# YOTSUBA_AP_EM_ver_1_1.net
KiCad netlist of a schematic drawn in EAGLE
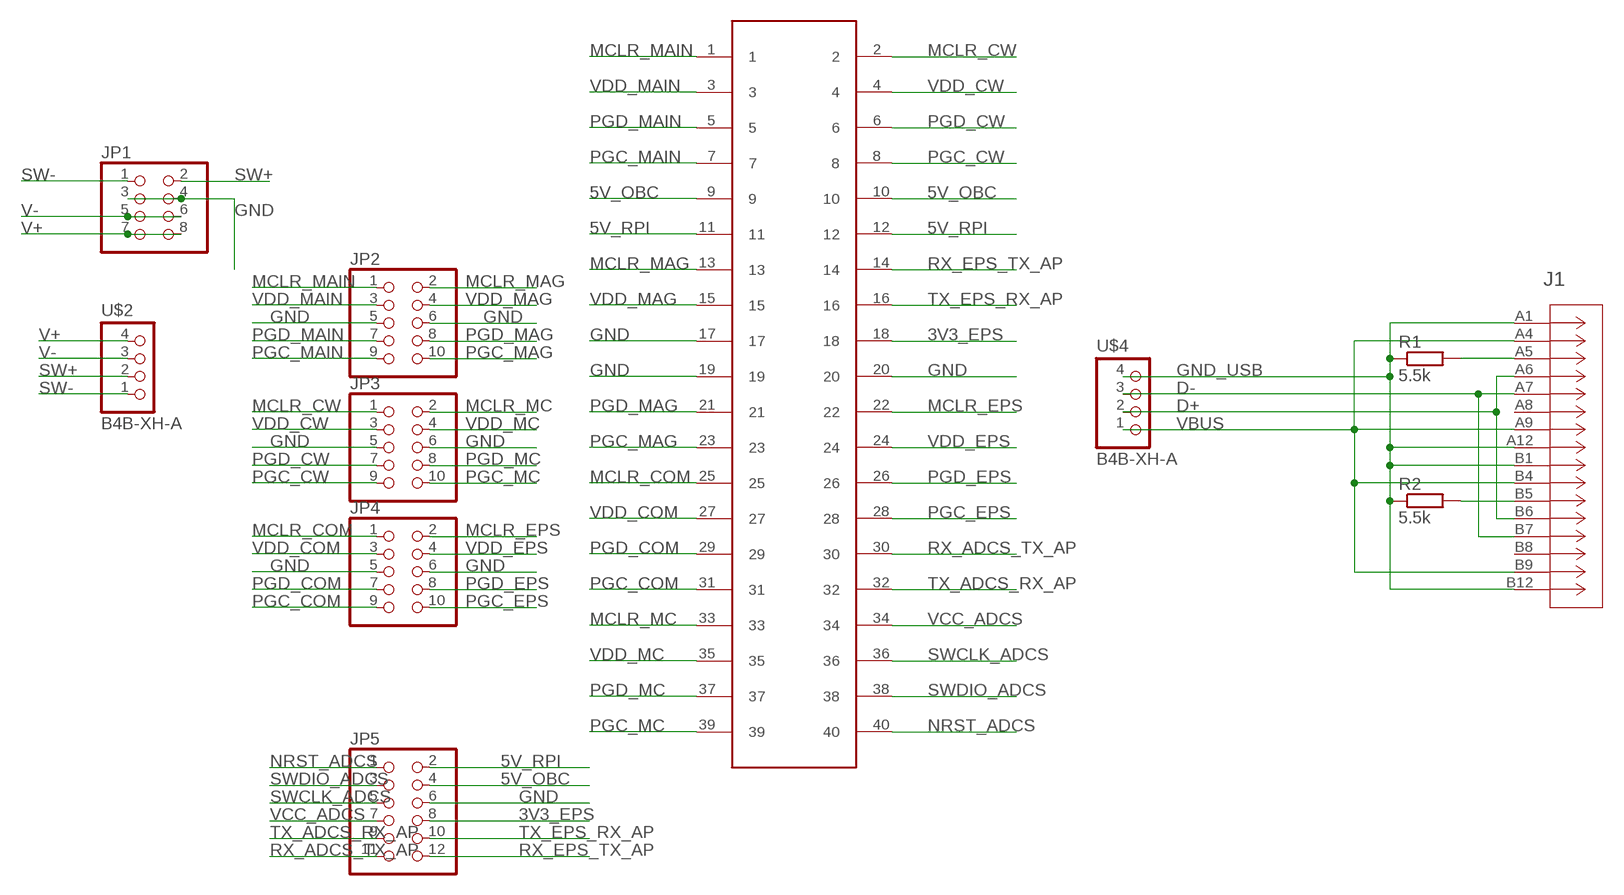
[diagram p0: schematic, sheet 1]

(export (version "E")
  (design (tool "Eeschema 10.0.6"))
  (components
    (comp (ref "J1")
      (value "217182-0001")
      (footprint "eagle-import:CONN_217182-0001_MOL")
      (fields (field (name "COPYRIGHT") "Copyright (C) 2022 Ultra Librarian. All rights reserved."))
      (libsource (lib "eagle-import") (part "217182-0001"))
    )
    (comp (ref "JP1")
      (value "PINHD-2X4")
      (footprint "eagle-import:2X04")
      (libsource (lib "eagle-import") (part "PINHD-2X4"))
    )
    (comp (ref "JP2")
      (value "PINHD-2X5")
      (footprint "eagle-import:2X05")
      (libsource (lib "eagle-import") (part "PINHD-2X5"))
    )
    (comp (ref "JP3")
      (value "PINHD-2X5")
      (footprint "eagle-import:2X05")
      (libsource (lib "eagle-import") (part "PINHD-2X5"))
    )
    (comp (ref "JP4")
      (value "PINHD-2X5")
      (footprint "eagle-import:2X05")
      (libsource (lib "eagle-import") (part "PINHD-2X5"))
    )
    (comp (ref "JP5")
      (value "PINHD-2X6")
      (footprint "eagle-import:2X06")
      (libsource (lib "eagle-import") (part "PINHD-2X6"))
    )
    (comp (ref "R1")
      (value "5.5k")
      (footprint "eagle-import:M2012")
      (libsource (lib "eagle-import") (part "R-EU_M2012"))
    )
    (comp (ref "R2")
      (value "5.5k")
      (footprint "eagle-import:M2012")
      (libsource (lib "eagle-import") (part "R-EU_M2012"))
    )
    (comp (ref "U$1")
      (value "M50-3902042")
      (footprint "eagle-import:M50-3902042")
      (libsource (lib "eagle-import") (part "M50-3902042"))
    )
    (comp (ref "U$2")
      (value "B4B-XH-A")
      (footprint "eagle-import:B4B-XH-A")
      (libsource (lib "eagle-import") (part "B4B-XH-A"))
    )
    (comp (ref "U$4")
      (value "B4B-XH-A")
      (footprint "eagle-import:B4B-XH-A")
      (libsource (lib "eagle-import") (part "B4B-XH-A"))
    )
  )
  (nets
    (net (code "1") (name "/3V3_EPS") (class "Default")
      (node (ref "JP5") (pin "8") (pinfunction "8_8") (pintype "passive"))
      (node (ref "U$1") (pin "18") (pinfunction "18_18") (pintype "bidirectional"))
    )
    (net (code "2") (name "/5V_OBC") (class "Default")
      (node (ref "JP5") (pin "4") (pinfunction "4_4") (pintype "passive"))
      (node (ref "U$1") (pin "10") (pinfunction "10_10") (pintype "bidirectional"))
      (node (ref "U$1") (pin "9") (pinfunction "9_9") (pintype "bidirectional"))
    )
    (net (code "3") (name "/5V_RPI") (class "Default")
      (node (ref "JP5") (pin "2") (pinfunction "2_2") (pintype "passive"))
      (node (ref "U$1") (pin "11") (pinfunction "11_11") (pintype "bidirectional"))
      (node (ref "U$1") (pin "12") (pinfunction "12_12") (pintype "bidirectional"))
    )
    (net (code "4") (name "/D+") (class "Default")
      (node (ref "J1") (pin "A6") (pinfunction "DP1_A6") (pintype "bidirectional"))
      (node (ref "J1") (pin "B6") (pinfunction "DP2_B6") (pintype "bidirectional"))
      (node (ref "U$4") (pin "2") (pinfunction "2_2") (pintype "passive"))
    )
    (net (code "5") (name "/D-") (class "Default")
      (node (ref "J1") (pin "A7") (pinfunction "DN1_A7") (pintype "bidirectional"))
      (node (ref "J1") (pin "B7") (pinfunction "DN2_B7") (pintype "bidirectional"))
      (node (ref "U$4") (pin "3") (pinfunction "3_3") (pintype "passive"))
    )
    (net (code "6") (name "/GND") (class "Default")
      (node (ref "JP1") (pin "3") (pinfunction "3_3") (pintype "passive"))
      (node (ref "JP1") (pin "4") (pinfunction "4_4") (pintype "passive"))
      (node (ref "JP2") (pin "5") (pinfunction "5_5") (pintype "passive"))
      (node (ref "JP2") (pin "6") (pinfunction "6_6") (pintype "passive"))
      (node (ref "JP3") (pin "5") (pinfunction "5_5") (pintype "passive"))
      (node (ref "JP3") (pin "6") (pinfunction "6_6") (pintype "passive"))
      (node (ref "JP4") (pin "5") (pinfunction "5_5") (pintype "passive"))
      (node (ref "JP4") (pin "6") (pinfunction "6_6") (pintype "passive"))
      (node (ref "JP5") (pin "6") (pinfunction "6_6") (pintype "passive"))
      (node (ref "U$1") (pin "17") (pinfunction "17_17") (pintype "bidirectional"))
      (node (ref "U$1") (pin "19") (pinfunction "19_19") (pintype "bidirectional"))
      (node (ref "U$1") (pin "20") (pinfunction "20_20") (pintype "bidirectional"))
    )
    (net (code "7") (name "/GND_USB") (class "Default")
      (node (ref "J1") (pin "A1") (pinfunction "GND_2_A1") (pintype "passive"))
      (node (ref "J1") (pin "A12") (pinfunction "GND_3_A12") (pintype "passive"))
      (node (ref "J1") (pin "B1") (pinfunction "GND_4_B1") (pintype "passive"))
      (node (ref "J1") (pin "B12") (pinfunction "GND_B12") (pintype "passive"))
      (node (ref "R1") (pin "1") (pinfunction "1_1") (pintype "passive"))
      (node (ref "R2") (pin "1") (pinfunction "1_1") (pintype "passive"))
      (node (ref "U$4") (pin "4") (pinfunction "4_4") (pintype "passive"))
    )
    (net (code "8") (name "/MCLR_COM") (class "Default")
      (node (ref "JP4") (pin "1") (pinfunction "1_1") (pintype "passive"))
      (node (ref "U$1") (pin "25") (pinfunction "25_25") (pintype "bidirectional"))
    )
    (net (code "9") (name "/MCLR_CW") (class "Default")
      (node (ref "JP3") (pin "1") (pinfunction "1_1") (pintype "passive"))
      (node (ref "U$1") (pin "2") (pinfunction "2_2") (pintype "bidirectional"))
    )
    (net (code "10") (name "/MCLR_EPS") (class "Default")
      (node (ref "JP4") (pin "2") (pinfunction "2_2") (pintype "passive"))
      (node (ref "U$1") (pin "22") (pinfunction "22_22") (pintype "bidirectional"))
    )
    (net (code "11") (name "/MCLR_MAG") (class "Default")
      (node (ref "JP2") (pin "2") (pinfunction "2_2") (pintype "passive"))
      (node (ref "U$1") (pin "13") (pinfunction "13_13") (pintype "bidirectional"))
    )
    (net (code "12") (name "/MCLR_MAIN") (class "Default")
      (node (ref "JP2") (pin "1") (pinfunction "1_1") (pintype "passive"))
      (node (ref "U$1") (pin "1") (pinfunction "1_1") (pintype "bidirectional"))
    )
    (net (code "13") (name "/MCLR_MC") (class "Default")
      (node (ref "JP3") (pin "2") (pinfunction "2_2") (pintype "passive"))
      (node (ref "U$1") (pin "33") (pinfunction "33_33") (pintype "bidirectional"))
    )
    (net (code "14") (name "/NRST_ADCS") (class "Default")
      (node (ref "JP5") (pin "1") (pinfunction "1_1") (pintype "passive"))
      (node (ref "U$1") (pin "40") (pinfunction "40_40") (pintype "bidirectional"))
    )
    (net (code "15") (name "/PGC_COM") (class "Default")
      (node (ref "JP4") (pin "9") (pinfunction "9_9") (pintype "passive"))
      (node (ref "U$1") (pin "31") (pinfunction "31_31") (pintype "bidirectional"))
    )
    (net (code "16") (name "/PGC_CW") (class "Default")
      (node (ref "JP3") (pin "9") (pinfunction "9_9") (pintype "passive"))
      (node (ref "U$1") (pin "8") (pinfunction "8_8") (pintype "bidirectional"))
    )
    (net (code "17") (name "/PGC_EPS") (class "Default")
      (node (ref "JP4") (pin "10") (pinfunction "10_10") (pintype "passive"))
      (node (ref "U$1") (pin "28") (pinfunction "28_28") (pintype "bidirectional"))
    )
    (net (code "18") (name "/PGC_MAG") (class "Default")
      (node (ref "JP2") (pin "10") (pinfunction "10_10") (pintype "passive"))
      (node (ref "U$1") (pin "23") (pinfunction "23_23") (pintype "bidirectional"))
    )
    (net (code "19") (name "/PGC_MAIN") (class "Default")
      (node (ref "JP2") (pin "9") (pinfunction "9_9") (pintype "passive"))
      (node (ref "U$1") (pin "7") (pinfunction "7_7") (pintype "bidirectional"))
    )
    (net (code "20") (name "/PGC_MC") (class "Default")
      (node (ref "JP3") (pin "10") (pinfunction "10_10") (pintype "passive"))
      (node (ref "U$1") (pin "39") (pinfunction "39_39") (pintype "bidirectional"))
    )
    (net (code "21") (name "/PGD_COM") (class "Default")
      (node (ref "JP4") (pin "7") (pinfunction "7_7") (pintype "passive"))
      (node (ref "U$1") (pin "29") (pinfunction "29_29") (pintype "bidirectional"))
    )
    (net (code "22") (name "/PGD_CW") (class "Default")
      (node (ref "JP3") (pin "7") (pinfunction "7_7") (pintype "passive"))
      (node (ref "U$1") (pin "6") (pinfunction "6_6") (pintype "bidirectional"))
    )
    (net (code "23") (name "/PGD_EPS") (class "Default")
      (node (ref "JP4") (pin "8") (pinfunction "8_8") (pintype "passive"))
      (node (ref "U$1") (pin "26") (pinfunction "26_26") (pintype "bidirectional"))
    )
    (net (code "24") (name "/PGD_MAG") (class "Default")
      (node (ref "JP2") (pin "8") (pinfunction "8_8") (pintype "passive"))
      (node (ref "U$1") (pin "21") (pinfunction "21_21") (pintype "bidirectional"))
    )
    (net (code "25") (name "/PGD_MAIN") (class "Default")
      (node (ref "JP2") (pin "7") (pinfunction "7_7") (pintype "passive"))
      (node (ref "U$1") (pin "5") (pinfunction "5_5") (pintype "bidirectional"))
    )
    (net (code "26") (name "/PGD_MC") (class "Default")
      (node (ref "JP3") (pin "8") (pinfunction "8_8") (pintype "passive"))
      (node (ref "U$1") (pin "37") (pinfunction "37_37") (pintype "bidirectional"))
    )
    (net (code "27") (name "/RX_ADCS_TX_AP") (class "Default")
      (node (ref "JP5") (pin "11") (pinfunction "11_11") (pintype "passive"))
      (node (ref "U$1") (pin "30") (pinfunction "30_30") (pintype "bidirectional"))
    )
    (net (code "28") (name "/RX_EPS_TX_AP") (class "Default")
      (node (ref "JP5") (pin "12") (pinfunction "12_12") (pintype "passive"))
      (node (ref "U$1") (pin "14") (pinfunction "14_14") (pintype "bidirectional"))
    )
    (net (code "29") (name "/SW+") (class "Default")
      (node (ref "JP1") (pin "2") (pinfunction "2_2") (pintype "passive"))
      (node (ref "U$2") (pin "2") (pinfunction "2_2") (pintype "passive"))
    )
    (net (code "30") (name "/SW-") (class "Default")
      (node (ref "JP1") (pin "1") (pinfunction "1_1") (pintype "passive"))
      (node (ref "U$2") (pin "1") (pinfunction "1_1") (pintype "passive"))
    )
    (net (code "31") (name "/SWCLK_ADCS") (class "Default")
      (node (ref "JP5") (pin "5") (pinfunction "5_5") (pintype "passive"))
      (node (ref "U$1") (pin "36") (pinfunction "36_36") (pintype "bidirectional"))
    )
    (net (code "32") (name "/SWDIO_ADCS") (class "Default")
      (node (ref "JP5") (pin "3") (pinfunction "3_3") (pintype "passive"))
      (node (ref "U$1") (pin "38") (pinfunction "38_38") (pintype "bidirectional"))
    )
    (net (code "33") (name "/TX_ADCS_RX_AP") (class "Default")
      (node (ref "JP5") (pin "9") (pinfunction "9_9") (pintype "passive"))
      (node (ref "U$1") (pin "32") (pinfunction "32_32") (pintype "bidirectional"))
    )
    (net (code "34") (name "/TX_EPS_RX_AP") (class "Default")
      (node (ref "JP5") (pin "10") (pinfunction "10_10") (pintype "passive"))
      (node (ref "U$1") (pin "16") (pinfunction "16_16") (pintype "bidirectional"))
    )
    (net (code "35") (name "/V+") (class "Default")
      (node (ref "JP1") (pin "7") (pinfunction "7_7") (pintype "passive"))
      (node (ref "JP1") (pin "8") (pinfunction "8_8") (pintype "passive"))
      (node (ref "U$2") (pin "4") (pinfunction "4_4") (pintype "passive"))
    )
    (net (code "36") (name "/V-") (class "Default")
      (node (ref "JP1") (pin "5") (pinfunction "5_5") (pintype "passive"))
      (node (ref "JP1") (pin "6") (pinfunction "6_6") (pintype "passive"))
      (node (ref "U$2") (pin "3") (pinfunction "3_3") (pintype "passive"))
    )
    (net (code "37") (name "/VBUS") (class "Default")
      (node (ref "J1") (pin "A4") (pinfunction "VBUS_2_A4") (pintype "passive"))
      (node (ref "J1") (pin "A9") (pinfunction "VBUS_3_A9") (pintype "passive"))
      (node (ref "J1") (pin "B4") (pinfunction "VBUS_4_B4") (pintype "passive"))
      (node (ref "J1") (pin "B9") (pinfunction "VBUS_B9") (pintype "passive"))
      (node (ref "U$4") (pin "1") (pinfunction "1_1") (pintype "passive"))
    )
    (net (code "38") (name "/VCC_ADCS") (class "Default")
      (node (ref "JP5") (pin "7") (pinfunction "7_7") (pintype "passive"))
      (node (ref "U$1") (pin "34") (pinfunction "34_34") (pintype "bidirectional"))
    )
    (net (code "39") (name "/VDD_COM") (class "Default")
      (node (ref "JP4") (pin "3") (pinfunction "3_3") (pintype "passive"))
      (node (ref "U$1") (pin "27") (pinfunction "27_27") (pintype "bidirectional"))
    )
    (net (code "40") (name "/VDD_CW") (class "Default")
      (node (ref "JP3") (pin "3") (pinfunction "3_3") (pintype "passive"))
      (node (ref "U$1") (pin "4") (pinfunction "4_4") (pintype "bidirectional"))
    )
    (net (code "41") (name "/VDD_EPS") (class "Default")
      (node (ref "JP4") (pin "4") (pinfunction "4_4") (pintype "passive"))
      (node (ref "U$1") (pin "24") (pinfunction "24_24") (pintype "bidirectional"))
    )
    (net (code "42") (name "/VDD_MAG") (class "Default")
      (node (ref "JP2") (pin "4") (pinfunction "4_4") (pintype "passive"))
      (node (ref "U$1") (pin "15") (pinfunction "15_15") (pintype "bidirectional"))
    )
    (net (code "43") (name "/VDD_MAIN") (class "Default")
      (node (ref "JP2") (pin "3") (pinfunction "3_3") (pintype "passive"))
      (node (ref "U$1") (pin "3") (pinfunction "3_3") (pintype "bidirectional"))
    )
    (net (code "44") (name "/VDD_MC") (class "Default")
      (node (ref "JP3") (pin "4") (pinfunction "4_4") (pintype "passive"))
      (node (ref "U$1") (pin "35") (pinfunction "35_35") (pintype "bidirectional"))
    )
    (net (code "45") (name "Net-(J1-CC1)") (class "Default")
      (node (ref "J1") (pin "A5") (pinfunction "CC1_A5") (pintype "bidirectional"))
      (node (ref "R1") (pin "2") (pinfunction "2_2") (pintype "passive"))
    )
    (net (code "46") (name "Net-(J1-CC2)") (class "Default")
      (node (ref "J1") (pin "B5") (pinfunction "CC2_B5") (pintype "bidirectional"))
      (node (ref "R2") (pin "2") (pinfunction "2_2") (pintype "passive"))
    )
    (net (code "47") (name "unconnected-(J1-SBU1-PadA8)") (class "Default")
      (node (ref "J1") (pin "A8") (pinfunction "SBU1_A8") (pintype "bidirectional"))
    )
    (net (code "48") (name "unconnected-(J1-SBU2-PadB8)") (class "Default")
      (node (ref "J1") (pin "B8") (pinfunction "SBU2_B8") (pintype "bidirectional"))
    )
  )
)
